# esp8266-dimmer.net
KiCad netlist of a schematic drawn in EAGLE
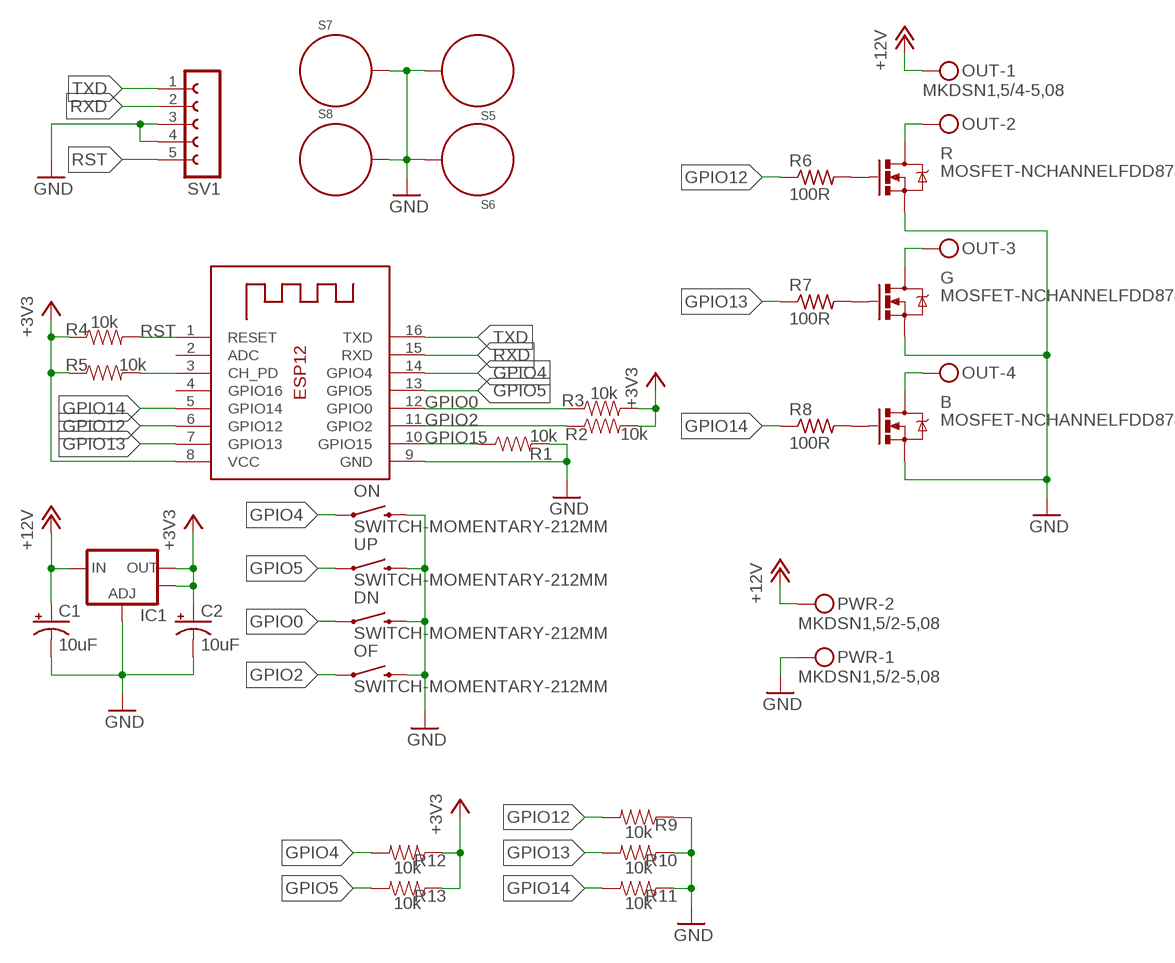
[diagram p0: schematic, sheet 1]

(export (version "E")
  (design (tool "Eeschema 10.0.6"))
  (components
    (comp (ref "B")
      (value "MOSFET-NCHANNELFDD8780")
      (footprint "eagle-import:DPAK")
      (libsource (lib "eagle-import") (part "MOSFET-NCHANNELFDD8780"))
    )
    (comp (ref "C1")
      (value "10uF")
      (footprint "eagle-import:EIA3216-KIT")
      (libsource (lib "eagle-import") (part "CAP_POL1206-KIT"))
    )
    (comp (ref "C2")
      (value "10uF")
      (footprint "eagle-import:EIA3216-KIT")
      (libsource (lib "eagle-import") (part "CAP_POL1206-KIT"))
    )
    (comp (ref "DN")
      (value "SWITCH-MOMENTARY-212MM")
      (footprint "eagle-import:TACTILE-PTH-12MM")
      (libsource (lib "eagle-import") (part "SWITCH-MOMENTARY-212MM"))
    )
    (comp (ref "ESP-12E")
      (value "ESP-12")
      (footprint "eagle-import:ESP-12")
      (libsource (lib "eagle-import") (part "ESP-12"))
    )
    (comp (ref "G")
      (value "MOSFET-NCHANNELFDD8780")
      (footprint "eagle-import:DPAK")
      (libsource (lib "eagle-import") (part "MOSFET-NCHANNELFDD8780"))
    )
    (comp (ref "IC1")
      (value "V_REG_LM1117SOT223")
      (footprint "eagle-import:SOT223")
      (libsource (lib "eagle-import") (part "V_REG_LM1117SOT223"))
    )
    (comp (ref "OF")
      (value "SWITCH-MOMENTARY-212MM")
      (footprint "eagle-import:TACTILE-PTH-12MM")
      (libsource (lib "eagle-import") (part "SWITCH-MOMENTARY-212MM"))
    )
    (comp (ref "ON")
      (value "SWITCH-MOMENTARY-212MM")
      (footprint "eagle-import:TACTILE-PTH-12MM")
      (libsource (lib "eagle-import") (part "SWITCH-MOMENTARY-212MM"))
    )
    (comp (ref "OUT")
      (value "MKDSN1,5/4-5,08")
      (footprint "eagle-import:MKDSN1,5_4-5,08")
      (libsource (lib "eagle-import") (part "MKDSN1,5/4-5,08"))
    )
    (comp (ref "PWR")
      (value "MKDSN1,5/2-5,08")
      (footprint "eagle-import:MKDSN1,5_2-5,08")
      (libsource (lib "eagle-import") (part "MKDSN1,5/2-5,08"))
    )
    (comp (ref "R")
      (value "MOSFET-NCHANNELFDD8780")
      (footprint "eagle-import:DPAK")
      (libsource (lib "eagle-import") (part "MOSFET-NCHANNELFDD8780"))
    )
    (comp (ref "R1")
      (value "10k")
      (footprint "eagle-import:0805")
      (libsource (lib "eagle-import") (part "RESISTOR0805-RES"))
    )
    (comp (ref "R2")
      (value "10k")
      (footprint "eagle-import:0805")
      (libsource (lib "eagle-import") (part "RESISTOR0805-RES"))
    )
    (comp (ref "R3")
      (value "10k")
      (footprint "eagle-import:0805")
      (libsource (lib "eagle-import") (part "RESISTOR0805-RES"))
    )
    (comp (ref "R4")
      (value "10k")
      (footprint "eagle-import:0805")
      (libsource (lib "eagle-import") (part "RESISTOR0805-RES"))
    )
    (comp (ref "R5")
      (value "10k")
      (footprint "eagle-import:0805")
      (libsource (lib "eagle-import") (part "RESISTOR0805-RES"))
    )
    (comp (ref "R6")
      (value "100R")
      (footprint "eagle-import:0805-THM-7")
      (libsource (lib "eagle-import") (part "R-US_FLIPFLOP7"))
    )
    (comp (ref "R7")
      (value "100R")
      (footprint "eagle-import:0805-THM-7")
      (libsource (lib "eagle-import") (part "R-US_FLIPFLOP7"))
    )
    (comp (ref "R8")
      (value "100R")
      (footprint "eagle-import:0805-THM-7")
      (libsource (lib "eagle-import") (part "R-US_FLIPFLOP7"))
    )
    (comp (ref "R9")
      (value "10k")
      (footprint "eagle-import:0805")
      (libsource (lib "eagle-import") (part "RESISTOR0805-RES"))
    )
    (comp (ref "R10")
      (value "10k")
      (footprint "eagle-import:0805")
      (libsource (lib "eagle-import") (part "RESISTOR0805-RES"))
    )
    (comp (ref "R11")
      (value "10k")
      (footprint "eagle-import:0805")
      (libsource (lib "eagle-import") (part "RESISTOR0805-RES"))
    )
    (comp (ref "R12")
      (value "10k")
      (footprint "eagle-import:0805")
      (libsource (lib "eagle-import") (part "RESISTOR0805-RES"))
    )
    (comp (ref "R13")
      (value "10k")
      (footprint "eagle-import:0805")
      (libsource (lib "eagle-import") (part "RESISTOR0805-RES"))
    )
    (comp (ref "S5")
      (value "STANDOFF_ELECTRICAL")
      (footprint "eagle-import:STANDOFF-ELECTRICAL")
      (libsource (lib "eagle-import") (part "STANDOFF_ELECTRICAL"))
    )
    (comp (ref "S6")
      (value "STANDOFF_ELECTRICAL")
      (footprint "eagle-import:STANDOFF-ELECTRICAL")
      (libsource (lib "eagle-import") (part "STANDOFF_ELECTRICAL"))
    )
    (comp (ref "S7")
      (value "STANDOFF_ELECTRICAL")
      (footprint "eagle-import:STANDOFF-ELECTRICAL")
      (libsource (lib "eagle-import") (part "STANDOFF_ELECTRICAL"))
    )
    (comp (ref "S8")
      (value "STANDOFF_ELECTRICAL")
      (footprint "eagle-import:STANDOFF-ELECTRICAL")
      (libsource (lib "eagle-import") (part "STANDOFF_ELECTRICAL"))
    )
    (comp (ref "SV1")
      (value "FE05W")
      (footprint "eagle-import:FE05W")
      (libsource (lib "eagle-import") (part "FE05W"))
    )
    (comp (ref "UP")
      (value "SWITCH-MOMENTARY-212MM")
      (footprint "eagle-import:TACTILE-PTH-12MM")
      (libsource (lib "eagle-import") (part "SWITCH-MOMENTARY-212MM"))
    )
  )
  (nets
    (net (code "1") (name "+3V3") (class "Default")
      (node (ref "C2") (pin "A") (pinfunction "+_A") (pintype "passive"))
      (node (ref "ESP-12E") (pin "8") (pinfunction "VCC_8") (pintype "power_in"))
      (node (ref "IC1") (pin "2") (pinfunction "OUT_2") (pintype "output"))
      (node (ref "IC1") (pin "4") (pinfunction "OUT_4") (pintype "output"))
      (node (ref "R12") (pin "1") (pinfunction "1_1") (pintype "passive"))
      (node (ref "R13") (pin "1") (pinfunction "1_1") (pintype "passive"))
      (node (ref "R2") (pin "2") (pinfunction "2_2") (pintype "passive"))
      (node (ref "R3") (pin "2") (pinfunction "2_2") (pintype "passive"))
      (node (ref "R4") (pin "1") (pinfunction "1_1") (pintype "passive"))
      (node (ref "R5") (pin "1") (pinfunction "1_1") (pintype "passive"))
    )
    (net (code "2") (name "+12V") (class "Default")
      (node (ref "C1") (pin "A") (pinfunction "+_A") (pintype "passive"))
      (node (ref "IC1") (pin "3") (pinfunction "IN_3") (pintype "input"))
      (node (ref "OUT") (pin "1") (pinfunction "KL_1") (pintype "passive"))
      (node (ref "PWR") (pin "2") (pinfunction "KL_2") (pintype "passive"))
    )
    (net (code "3") (name "/GPIO15") (class "Default")
      (node (ref "ESP-12E") (pin "10") (pinfunction "GPIO15_10") (pintype "bidirectional"))
      (node (ref "R1") (pin "1") (pinfunction "1_1") (pintype "passive"))
    )
    (net (code "4") (name "GND") (class "Default")
      (node (ref "B") (pin "3") (pinfunction "S_3") (pintype "passive"))
      (node (ref "C1") (pin "C") (pinfunction "-_C") (pintype "passive"))
      (node (ref "C2") (pin "C") (pinfunction "-_C") (pintype "passive"))
      (node (ref "DN") (pin "3") (pinfunction "2_3") (pintype "passive"))
      (node (ref "ESP-12E") (pin "9") (pinfunction "GND_9") (pintype "power_in"))
      (node (ref "G") (pin "3") (pinfunction "S_3") (pintype "passive"))
      (node (ref "IC1") (pin "1") (pinfunction "ADJ_1") (pintype "input"))
      (node (ref "OF") (pin "3") (pinfunction "2_3") (pintype "passive"))
      (node (ref "ON") (pin "3") (pinfunction "2_3") (pintype "passive"))
      (node (ref "PWR") (pin "1") (pinfunction "KL_1") (pintype "passive"))
      (node (ref "R") (pin "3") (pinfunction "S_3") (pintype "passive"))
      (node (ref "R1") (pin "2") (pinfunction "2_2") (pintype "passive"))
      (node (ref "R10") (pin "1") (pinfunction "1_1") (pintype "passive"))
      (node (ref "R11") (pin "1") (pinfunction "1_1") (pintype "passive"))
      (node (ref "R9") (pin "1") (pinfunction "1_1") (pintype "passive"))
      (node (ref "S5") (pin "P1") (pinfunction "P$1_P1") (pintype "bidirectional"))
      (node (ref "S6") (pin "P1") (pinfunction "P$1_P1") (pintype "bidirectional"))
      (node (ref "S7") (pin "P1") (pinfunction "P$1_P1") (pintype "bidirectional"))
      (node (ref "S8") (pin "P1") (pinfunction "P$1_P1") (pintype "bidirectional"))
      (node (ref "SV1") (pin "3") (pinfunction "3_3") (pintype "passive"))
      (node (ref "SV1") (pin "4") (pinfunction "4_4") (pintype "passive"))
      (node (ref "UP") (pin "3") (pinfunction "2_3") (pintype "passive"))
    )
    (net (code "5") (name "GPIO0") (class "Default")
      (node (ref "DN") (pin "1") (pinfunction "1_1") (pintype "passive"))
      (node (ref "ESP-12E") (pin "12") (pinfunction "GPIO0_12") (pintype "bidirectional"))
      (node (ref "R3") (pin "1") (pinfunction "1_1") (pintype "passive"))
    )
    (net (code "6") (name "GPIO2") (class "Default")
      (node (ref "ESP-12E") (pin "11") (pinfunction "GPIO2_11") (pintype "bidirectional"))
      (node (ref "OF") (pin "1") (pinfunction "1_1") (pintype "passive"))
      (node (ref "R2") (pin "1") (pinfunction "1_1") (pintype "passive"))
    )
    (net (code "7") (name "GPIO4") (class "Default")
      (node (ref "ESP-12E") (pin "14") (pinfunction "GPIO4_14") (pintype "bidirectional"))
      (node (ref "ON") (pin "1") (pinfunction "1_1") (pintype "passive"))
      (node (ref "R12") (pin "2") (pinfunction "2_2") (pintype "passive"))
    )
    (net (code "8") (name "GPIO5") (class "Default")
      (node (ref "ESP-12E") (pin "13") (pinfunction "GPIO5_13") (pintype "bidirectional"))
      (node (ref "R13") (pin "2") (pinfunction "2_2") (pintype "passive"))
      (node (ref "UP") (pin "1") (pinfunction "1_1") (pintype "passive"))
    )
    (net (code "9") (name "GPIO12") (class "Default")
      (node (ref "ESP-12E") (pin "6") (pinfunction "GPIO12_6") (pintype "bidirectional"))
      (node (ref "R6") (pin "1") (pinfunction "1_1") (pintype "passive"))
      (node (ref "R9") (pin "2") (pinfunction "2_2") (pintype "passive"))
    )
    (net (code "10") (name "GPIO13") (class "Default")
      (node (ref "ESP-12E") (pin "7") (pinfunction "GPIO13_7") (pintype "bidirectional"))
      (node (ref "R10") (pin "2") (pinfunction "2_2") (pintype "passive"))
      (node (ref "R7") (pin "1") (pinfunction "1_1") (pintype "passive"))
    )
    (net (code "11") (name "GPIO14") (class "Default")
      (node (ref "ESP-12E") (pin "5") (pinfunction "GPIO14_5") (pintype "bidirectional"))
      (node (ref "R11") (pin "2") (pinfunction "2_2") (pintype "passive"))
      (node (ref "R8") (pin "1") (pinfunction "1_1") (pintype "passive"))
    )
    (net (code "12") (name "Net-(B-D)") (class "Default")
      (node (ref "B") (pin "4") (pinfunction "D_4") (pintype "passive"))
      (node (ref "OUT") (pin "4") (pinfunction "KL_4") (pintype "passive"))
    )
    (net (code "13") (name "Net-(B-G)") (class "Default")
      (node (ref "B") (pin "1") (pinfunction "G_1") (pintype "passive"))
      (node (ref "R8") (pin "2") (pinfunction "2_2") (pintype "passive"))
    )
    (net (code "14") (name "Net-(ESP-12E-CH_PD)") (class "Default")
      (node (ref "ESP-12E") (pin "3") (pinfunction "CH_PD_3") (pintype "input"))
      (node (ref "R5") (pin "2") (pinfunction "2_2") (pintype "passive"))
    )
    (net (code "15") (name "Net-(G-D)") (class "Default")
      (node (ref "G") (pin "4") (pinfunction "D_4") (pintype "passive"))
      (node (ref "OUT") (pin "3") (pinfunction "KL_3") (pintype "passive"))
    )
    (net (code "16") (name "Net-(G-G)") (class "Default")
      (node (ref "G") (pin "1") (pinfunction "G_1") (pintype "passive"))
      (node (ref "R7") (pin "2") (pinfunction "2_2") (pintype "passive"))
    )
    (net (code "17") (name "Net-(OUTB-KL)") (class "Default")
      (node (ref "OUT") (pin "2") (pinfunction "KL_2") (pintype "passive"))
      (node (ref "R") (pin "4") (pinfunction "D_4") (pintype "passive"))
    )
    (net (code "18") (name "Net-(R-G)") (class "Default")
      (node (ref "R") (pin "1") (pinfunction "G_1") (pintype "passive"))
      (node (ref "R6") (pin "2") (pinfunction "2_2") (pintype "passive"))
    )
    (net (code "19") (name "RST") (class "Default")
      (node (ref "ESP-12E") (pin "1") (pinfunction "RESET_1") (pintype "input"))
      (node (ref "R4") (pin "2") (pinfunction "2_2") (pintype "passive"))
      (node (ref "SV1") (pin "5") (pinfunction "5_5") (pintype "passive"))
    )
    (net (code "20") (name "RXD") (class "Default")
      (node (ref "ESP-12E") (pin "15") (pinfunction "RXD_15") (pintype "input"))
      (node (ref "SV1") (pin "2") (pinfunction "2_2") (pintype "passive"))
    )
    (net (code "21") (name "TXD") (class "Default")
      (node (ref "ESP-12E") (pin "16") (pinfunction "TXD_16") (pintype "output"))
      (node (ref "SV1") (pin "1") (pinfunction "1_1") (pintype "passive"))
    )
    (net (code "22") (name "unconnected-(ESP-12E-ADC-Pad2)") (class "Default")
      (node (ref "ESP-12E") (pin "2") (pinfunction "ADC_2") (pintype "passive"))
    )
    (net (code "23") (name "unconnected-(ESP-12E-GPIO16-Pad4)") (class "Default")
      (node (ref "ESP-12E") (pin "4") (pinfunction "GPIO16_4") (pintype "bidirectional"))
    )
  )
)
